# Data_Conversion_TopBoard.net
KiCad netlist of a schematic drawn in Altium Designer
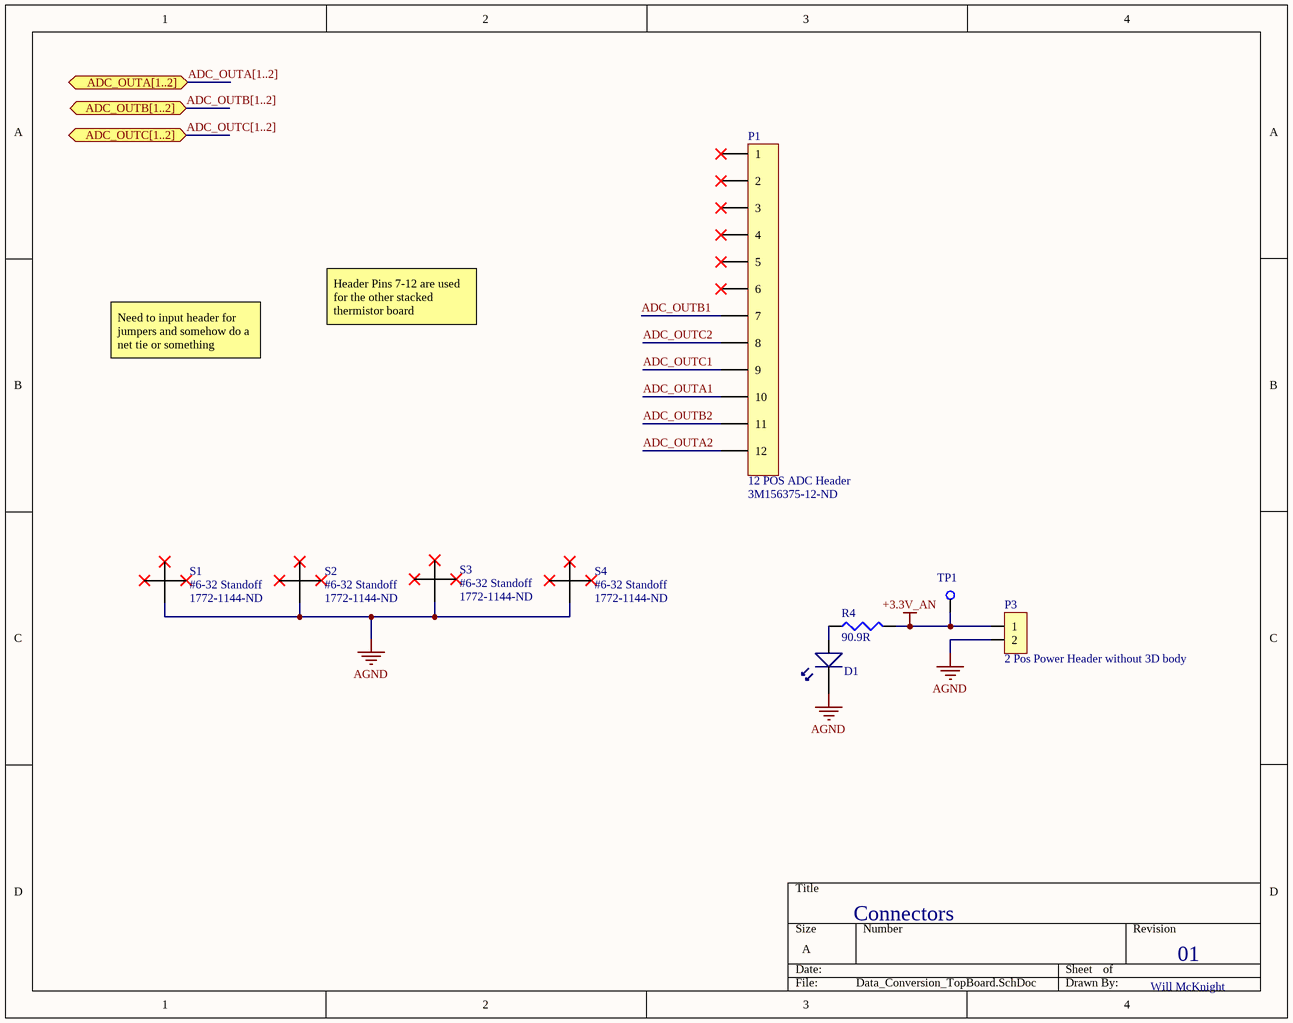
[diagram p0: Data_Conversion_TopBoard.SchDoc]

(export (version "E")
  (design (tool "Eeschema 10.0.6"))
  (components
    (comp (ref "D1")
      (value "LED")
      (footprint "Green_SMD_LED")
      (fields
        (field (name "MANUFACTURER") "Dialight")
        (field (name "MANUFACTURER PART NUMBER") "5988070107F")
      )
      (libsource (lib "Schematic_Library") (part "GREEN_LED"))
    )
    (comp (ref "P1")
      (value "12 POS ADC Header")
      (footprint "12 POS Dual Header")
      (description "Interboard connector for thermistors connecting to ADC")
      (fields
        (field (name "MANUFACTURER") "3M")
        (field (name "MANUFACTURER PART NUMBER") "929715-06-06-EU")
        (field (name "SUPPLIER PART NUMBER 1") "3M156375-12-ND")
      )
      (libsource (lib "Schematic_Library") (part "12 POS ADC Header"))
    )
    (comp (ref "P3")
      (value "2 Pos Power Header without 3D body")
      (footprint "2 Pos Power Header - duplicate")
      (libsource (lib "Schematic_Library") (part "2 Pos Power Header without 3D body"))
    )
    (comp (ref "R4")
      (value "Green")
      (footprint "Green_LED_Resistor_90.9")
      (fields
        (field (name "MANUFACTURER") "Panasonic")
        (field (name "MANUFACTURER PART NUMBER") "ERJ-1GNF90R9C")
        (field (name "TOLERANCE") "1%")
        (field (name "RESISTANCE") "90.9R")
      )
      (libsource (lib "Schematic_Library") (part "Green_LED_Res"))
    )
    (comp (ref "S1")
      (value "#6-32 Standoff")
      (footprint "#6-32 Stand Off")
      (description "Hex Standoff for Thermistor Boards")
      (fields
        (field (name "MANUFACTURER") "RAF")
        (field (name "MANUFACTURER PART NUMBER") "2102T-632-AL-7")
        (field (name "SUPPLIER PART NUMBER 1") "1772-1144-ND")
      )
      (libsource (lib "Schematic_Library") (part "#6-32 Standoff"))
    )
    (comp (ref "S2")
      (value "#6-32 Standoff")
      (footprint "#6-32 Stand Off")
      (description "Hex Standoff for Thermistor Boards")
      (fields
        (field (name "MANUFACTURER") "RAF")
        (field (name "MANUFACTURER PART NUMBER") "2102T-632-AL-7")
        (field (name "SUPPLIER PART NUMBER 1") "1772-1144-ND")
      )
      (libsource (lib "Schematic_Library") (part "#6-32 Standoff"))
    )
    (comp (ref "S3")
      (value "#6-32 Standoff")
      (footprint "#6-32 Stand Off")
      (description "Hex Standoff for Thermistor Boards")
      (fields
        (field (name "MANUFACTURER") "RAF")
        (field (name "MANUFACTURER PART NUMBER") "2102T-632-AL-7")
        (field (name "SUPPLIER PART NUMBER 1") "1772-1144-ND")
      )
      (libsource (lib "Schematic_Library") (part "#6-32 Standoff"))
    )
    (comp (ref "S4")
      (value "#6-32 Standoff")
      (footprint "#6-32 Stand Off")
      (description "Hex Standoff for Thermistor Boards")
      (fields
        (field (name "MANUFACTURER") "RAF")
        (field (name "MANUFACTURER PART NUMBER") "2102T-632-AL-7")
        (field (name "SUPPLIER PART NUMBER 1") "1772-1144-ND")
      )
      (libsource (lib "Schematic_Library") (part "#6-32 Standoff"))
    )
    (comp (ref "TP1")
      (value "Test Point")
      (footprint "Test Point")
      (libsource (lib "Schematic_Library") (part "Test Point"))
    )
  )
  (nets
    (net (code "1") (name "+3.3V_AN") (class "Default")
      (node (ref "P3") (pin "1") (pinfunction "1_1") (pintype "passive"))
      (node (ref "R4") (pin "2") (pinfunction "2_2") (pintype "passive"))
      (node (ref "TP1") (pin "1") (pinfunction "1_1") (pintype "passive"))
    )
    (net (code "2") (name "/ADC_OUTA1") (class "Default")
      (node (ref "P1") (pin "10") (pinfunction "10_10") (pintype "passive"))
    )
    (net (code "3") (name "/ADC_OUTA2") (class "Default")
      (node (ref "P1") (pin "12") (pinfunction "12_12") (pintype "passive"))
    )
    (net (code "5") (name "/ADC_OUTB1") (class "Default")
      (node (ref "P1") (pin "7") (pinfunction "7_7") (pintype "passive"))
    )
    (net (code "6") (name "/ADC_OUTB2") (class "Default")
      (node (ref "P1") (pin "11") (pinfunction "11_11") (pintype "passive"))
    )
    (net (code "8") (name "/ADC_OUTC1") (class "Default")
      (node (ref "P1") (pin "9") (pinfunction "9_9") (pintype "passive"))
    )
    (net (code "9") (name "/ADC_OUTC2") (class "Default")
      (node (ref "P1") (pin "8") (pinfunction "8_8") (pintype "passive"))
    )
    (net (code "11") (name "AGND") (class "Default")
      (node (ref "D1") (pin "1") (pinfunction "1_1") (pintype "passive"))
      (node (ref "P3") (pin "2") (pinfunction "2_2") (pintype "passive"))
      (node (ref "S1") (pin "1") (pinfunction "2_1") (pintype "passive"))
      (node (ref "S2") (pin "1") (pinfunction "2_1") (pintype "passive"))
      (node (ref "S3") (pin "1") (pinfunction "2_1") (pintype "passive"))
      (node (ref "S4") (pin "1") (pinfunction "2_1") (pintype "passive"))
    )
    (net (code "12") (name "Net-(D1-Pad2)") (class "Default")
      (node (ref "D1") (pin "2") (pinfunction "2_2") (pintype "passive"))
      (node (ref "R4") (pin "1") (pinfunction "1_1") (pintype "passive"))
    )
    (net (code "13") (name "unconnected-(P1-Pad1)") (class "Default")
      (node (ref "P1") (pin "1") (pinfunction "1_1") (pintype "passive+no_connect"))
    )
    (net (code "14") (name "unconnected-(P1-Pad2)") (class "Default")
      (node (ref "P1") (pin "2") (pinfunction "2_2") (pintype "passive+no_connect"))
    )
    (net (code "15") (name "unconnected-(P1-Pad3)") (class "Default")
      (node (ref "P1") (pin "3") (pinfunction "3_3") (pintype "passive+no_connect"))
    )
    (net (code "16") (name "unconnected-(P1-Pad4)") (class "Default")
      (node (ref "P1") (pin "4") (pinfunction "4_4") (pintype "passive+no_connect"))
    )
    (net (code "17") (name "unconnected-(P1-Pad5)") (class "Default")
      (node (ref "P1") (pin "5") (pinfunction "5_5") (pintype "passive+no_connect"))
    )
    (net (code "18") (name "unconnected-(P1-Pad6)") (class "Default")
      (node (ref "P1") (pin "6") (pinfunction "6_6") (pintype "passive+no_connect"))
    )
    (net (code "19") (name "unconnected-(S1-3-Pad1)") (class "Default")
      (node (ref "S1") (pin "1") (pinfunction "3_1") (pintype "passive+no_connect"))
    )
    (net (code "20") (name "unconnected-(S1-4-Pad1)") (class "Default")
      (node (ref "S1") (pin "1") (pinfunction "4_1") (pintype "passive+no_connect"))
    )
    (net (code "21") (name "unconnected-(S1-Pad1)") (class "Default")
      (node (ref "S1") (pin "1") (pinfunction "1_1") (pintype "passive+no_connect"))
    )
    (net (code "22") (name "unconnected-(S2-3-Pad1)") (class "Default")
      (node (ref "S2") (pin "1") (pinfunction "3_1") (pintype "passive+no_connect"))
    )
    (net (code "23") (name "unconnected-(S2-4-Pad1)") (class "Default")
      (node (ref "S2") (pin "1") (pinfunction "4_1") (pintype "passive+no_connect"))
    )
    (net (code "24") (name "unconnected-(S2-Pad1)") (class "Default")
      (node (ref "S2") (pin "1") (pinfunction "1_1") (pintype "passive+no_connect"))
    )
    (net (code "25") (name "unconnected-(S3-3-Pad1)") (class "Default")
      (node (ref "S3") (pin "1") (pinfunction "3_1") (pintype "passive+no_connect"))
    )
    (net (code "26") (name "unconnected-(S3-4-Pad1)") (class "Default")
      (node (ref "S3") (pin "1") (pinfunction "4_1") (pintype "passive+no_connect"))
    )
    (net (code "27") (name "unconnected-(S3-Pad1)") (class "Default")
      (node (ref "S3") (pin "1") (pinfunction "1_1") (pintype "passive+no_connect"))
    )
    (net (code "28") (name "unconnected-(S4-3-Pad1)") (class "Default")
      (node (ref "S4") (pin "1") (pinfunction "3_1") (pintype "passive+no_connect"))
    )
    (net (code "29") (name "unconnected-(S4-4-Pad1)") (class "Default")
      (node (ref "S4") (pin "1") (pinfunction "4_1") (pintype "passive+no_connect"))
    )
    (net (code "30") (name "unconnected-(S4-Pad1)") (class "Default")
      (node (ref "S4") (pin "1") (pinfunction "1_1") (pintype "passive+no_connect"))
    )
  )
)
